# ADC.net
KiCad netlist of a schematic drawn in Altium Designer
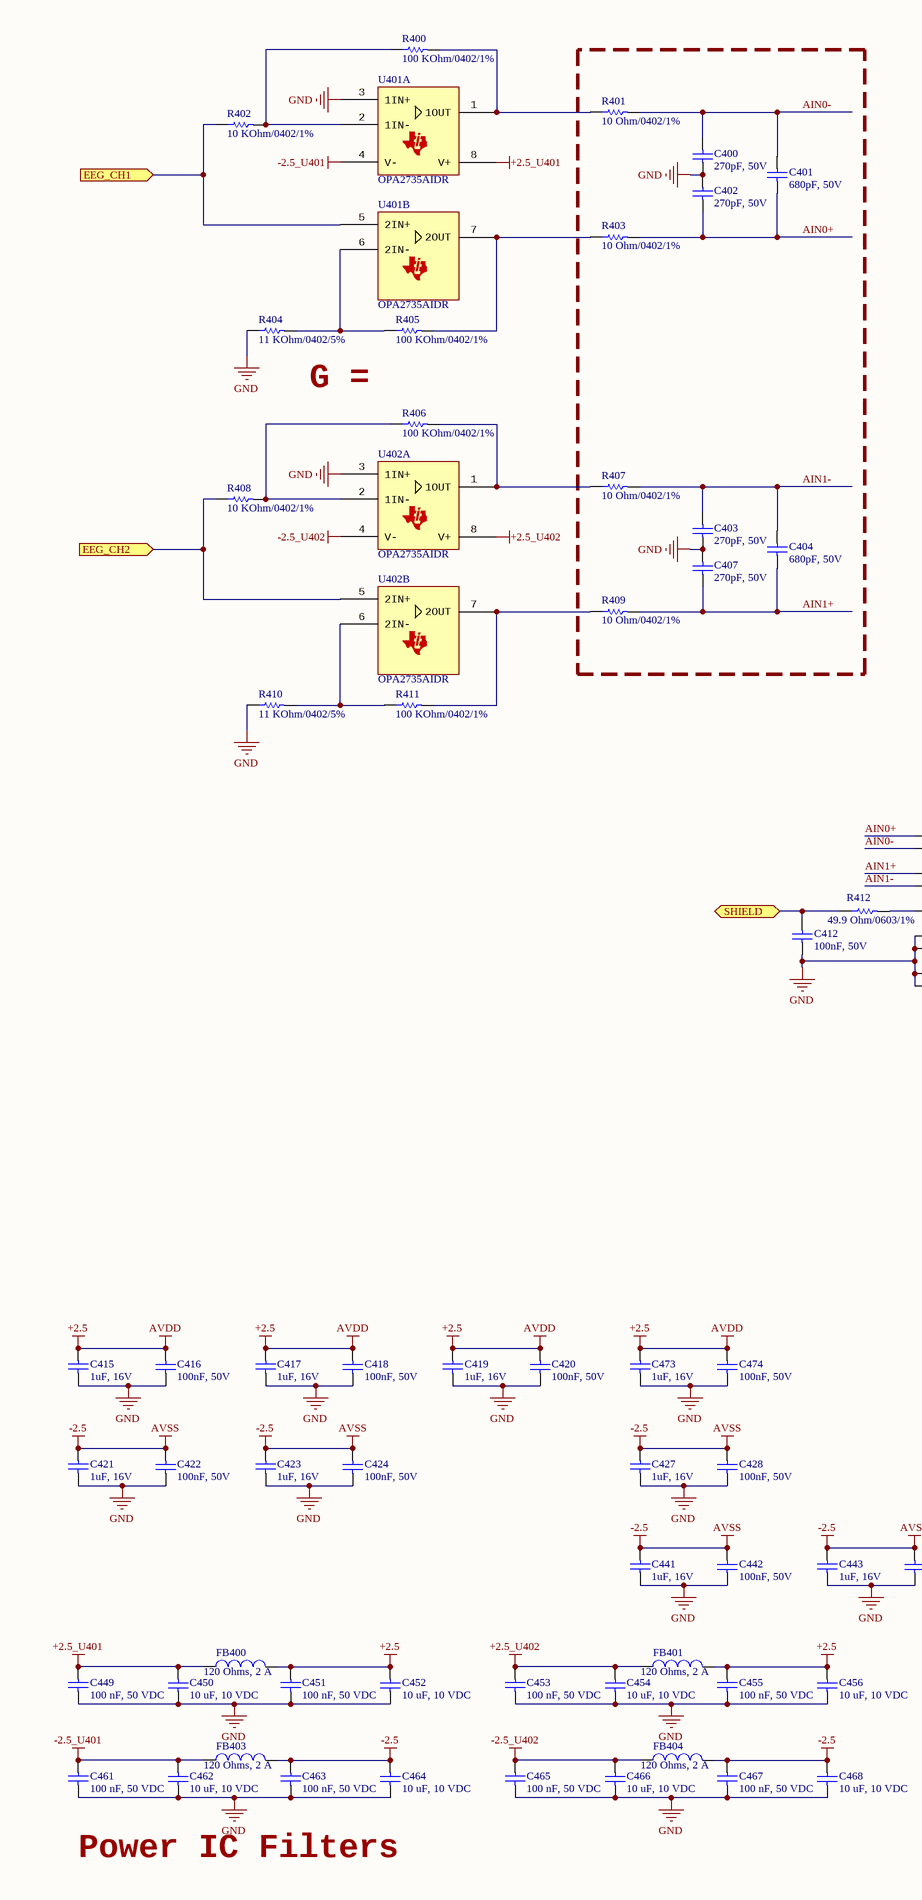
[diagram p0: ADC.SchDoc, left]
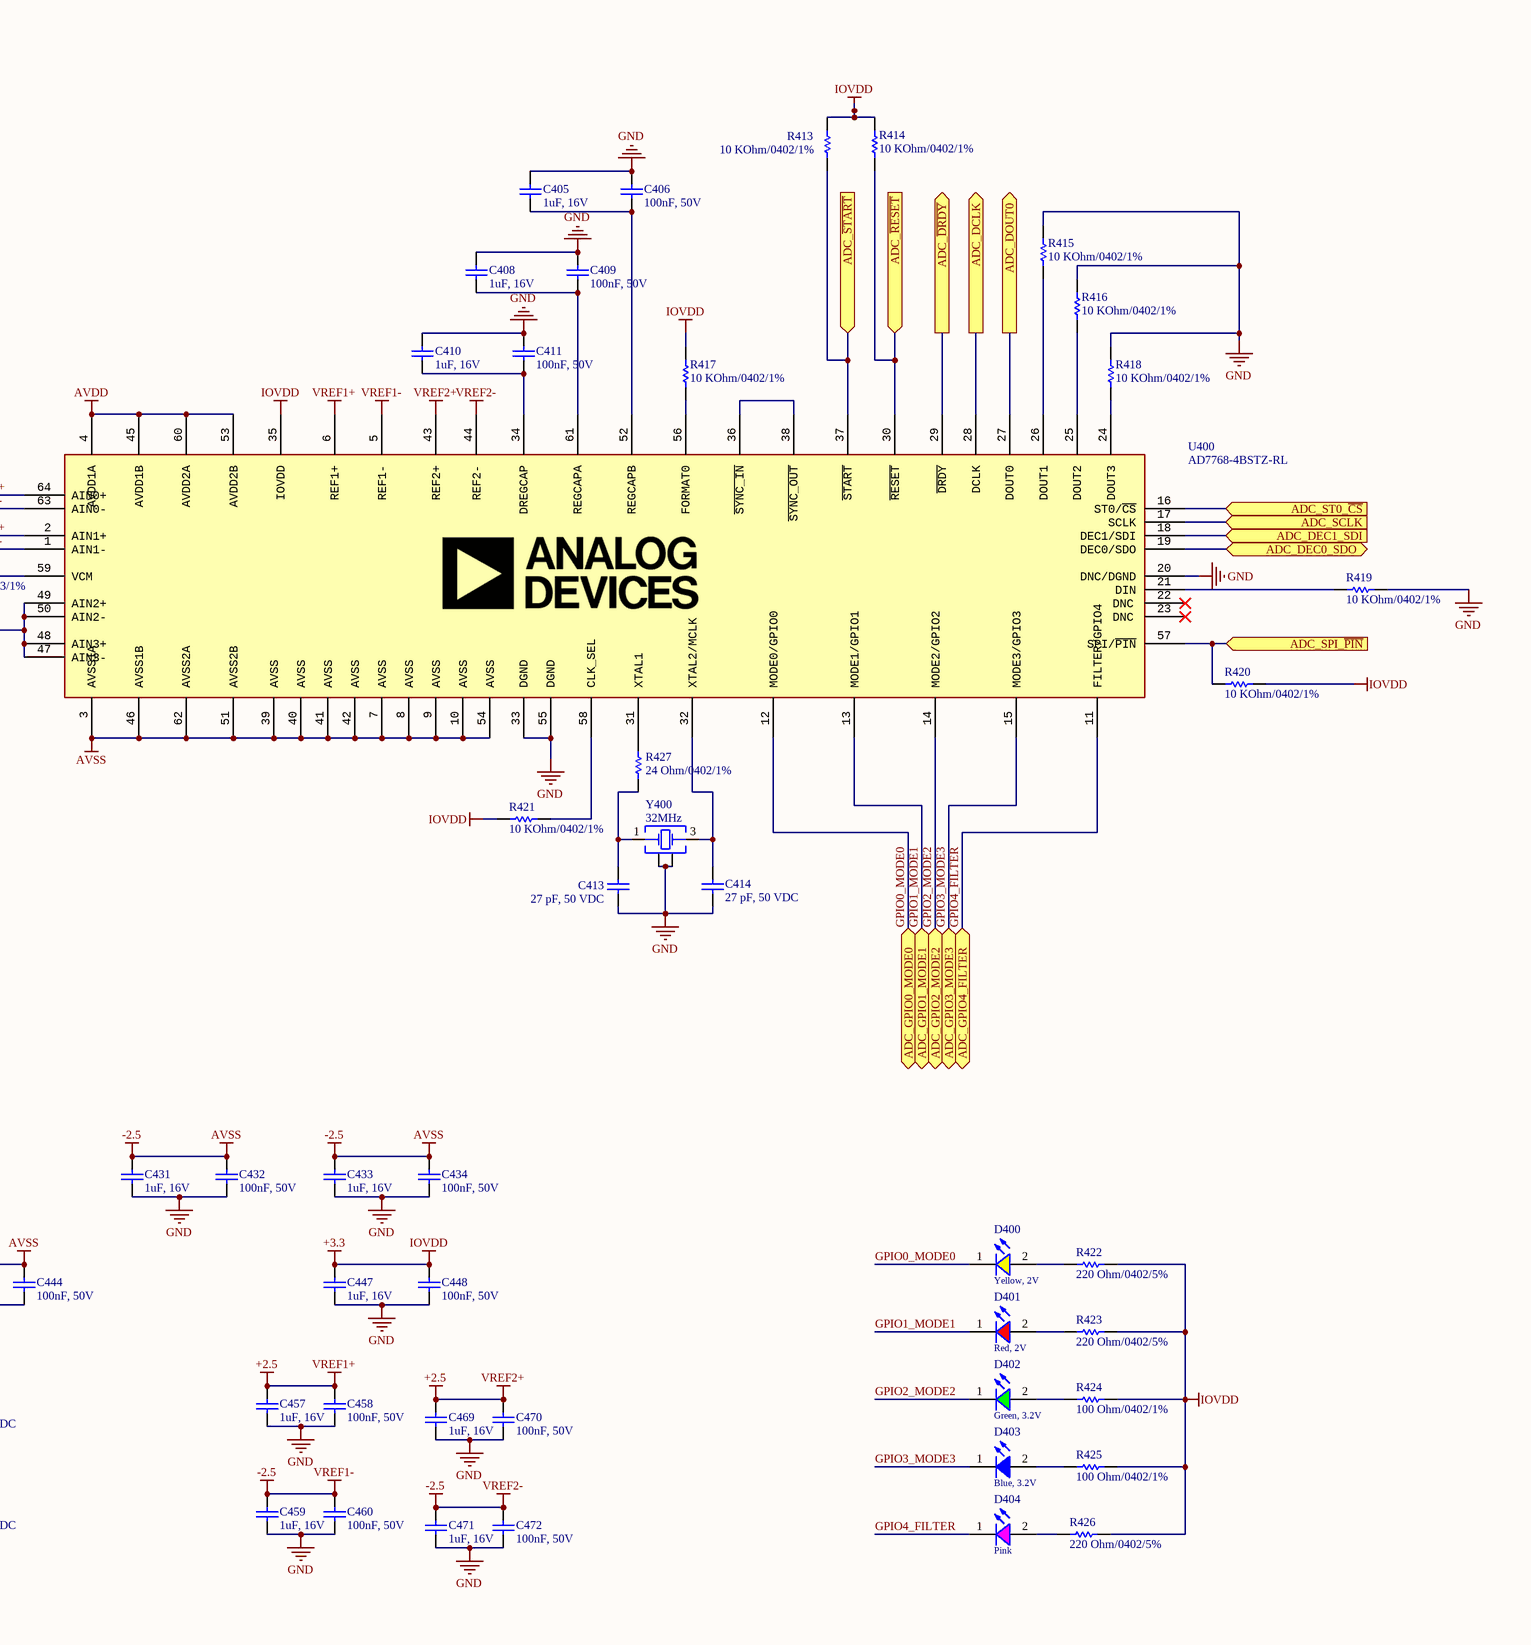
[diagram p1: ADC.SchDoc, right]

(export (version "E")
  (design (tool "Eeschema 10.0.6"))
  (components
    (comp (ref "C400")
      (value "270pF, 50V")
      (footprint "WCAP-CSGP_0402_L1W0.5H0.5")
      (description "WCAP-CSGP Multilayer Ceramic Chip Capacitor, General Purpose, size 0402, NP0, 270pF, 50V")
      (fields
        (field (name "MANUFACTURER PART NUMBER") "885012005063")
        (field (name "MANUFACTURER") "Wurth Elektronik")
      )
      (libsource (lib "Altium_WCAP-CSGP (rev24c)") (part "885012005063"))
    )
    (comp (ref "C401")
      (value "680pF, 50V")
      (footprint "WCAP-CSGP_0402_L1W0.5H0.5")
      (description "WCAP-CSGP Multilayer Ceramic Chip Capacitor, General Purpose, size 0402, X7R, 680pF, 50V")
      (fields
        (field (name "MANUFACTURER PART NUMBER") "885012205060")
        (field (name "MANUFACTURER") "Wurth Elektronik")
      )
      (libsource (lib "Altium_WCAP-CSGP (rev24c)") (part "885012205060"))
    )
    (comp (ref "C402")
      (value "270pF, 50V")
      (footprint "WCAP-CSGP_0402_L1W0.5H0.5")
      (description "WCAP-CSGP Multilayer Ceramic Chip Capacitor, General Purpose, size 0402, NP0, 270pF, 50V")
      (fields
        (field (name "MANUFACTURER PART NUMBER") "885012005063")
        (field (name "MANUFACTURER") "Wurth Elektronik")
      )
      (libsource (lib "Altium_WCAP-CSGP (rev24c)") (part "885012005063"))
    )
    (comp (ref "C403")
      (value "270pF, 50V")
      (footprint "WCAP-CSGP_0402_L1W0.5H0.5")
      (description "WCAP-CSGP Multilayer Ceramic Chip Capacitor, General Purpose, size 0402, NP0, 270pF, 50V")
      (fields
        (field (name "MANUFACTURER PART NUMBER") "885012005063")
        (field (name "MANUFACTURER") "Wurth Elektronik")
      )
      (libsource (lib "Altium_WCAP-CSGP (rev24c)") (part "885012005063"))
    )
    (comp (ref "C404")
      (value "680pF, 50V")
      (footprint "WCAP-CSGP_0402_L1W0.5H0.5")
      (description "WCAP-CSGP Multilayer Ceramic Chip Capacitor, General Purpose, size 0402, X7R, 680pF, 50V")
      (fields
        (field (name "MANUFACTURER PART NUMBER") "885012205060")
        (field (name "MANUFACTURER") "Wurth Elektronik")
      )
      (libsource (lib "Altium_WCAP-CSGP (rev24c)") (part "885012205060"))
    )
    (comp (ref "C405")
      (value "1uF, 16V")
      (footprint "WCAP-CSGP_0402_L1W0.5H0.5")
      (description "1 µF ±10% 16V Ceramic Capacitor X7R 0603 (1608 Metric)")
      (fields
        (field (name "MANUFACTURER PART NUMBER") "885012105012")
        (field (name "MANUFACTURER") "Wurth Elektronik")
      )
      (libsource (lib "Altium_WCAP-CSGP (rev24c)") (part "885012105012"))
    )
    (comp (ref "C406")
      (value "100nF, 50V")
      (footprint "WCAP-CSGP_0402_L1W0.5H0.5")
      (description "WCAP-CSGP Multilayer Ceramic Chip Capacitor, General Purpose, size 0402, X7R, 100nF, 50V")
      (fields
        (field (name "MANUFACTURER PART NUMBER") "885012205086")
        (field (name "MANUFACTURER") "Wurth Elektronik")
      )
      (libsource (lib "Altium_WCAP-CSGP (rev24c)") (part "885012205086"))
    )
    (comp (ref "C407")
      (value "270pF, 50V")
      (footprint "WCAP-CSGP_0402_L1W0.5H0.5")
      (description "WCAP-CSGP Multilayer Ceramic Chip Capacitor, General Purpose, size 0402, NP0, 270pF, 50V")
      (fields
        (field (name "MANUFACTURER PART NUMBER") "885012005063")
        (field (name "MANUFACTURER") "Wurth Elektronik")
      )
      (libsource (lib "Altium_WCAP-CSGP (rev24c)") (part "885012005063"))
    )
    (comp (ref "C408")
      (value "1uF, 16V")
      (footprint "WCAP-CSGP_0402_L1W0.5H0.5")
      (description "1 µF ±10% 16V Ceramic Capacitor X7R 0603 (1608 Metric)")
      (fields
        (field (name "MANUFACTURER PART NUMBER") "885012105012")
        (field (name "MANUFACTURER") "Wurth Elektronik")
      )
      (libsource (lib "Altium_WCAP-CSGP (rev24c)") (part "885012105012"))
    )
    (comp (ref "C409")
      (value "100nF, 50V")
      (footprint "WCAP-CSGP_0402_L1W0.5H0.5")
      (description "WCAP-CSGP Multilayer Ceramic Chip Capacitor, General Purpose, size 0402, X7R, 100nF, 50V")
      (fields
        (field (name "MANUFACTURER PART NUMBER") "885012205086")
        (field (name "MANUFACTURER") "Wurth Elektronik")
      )
      (libsource (lib "Altium_WCAP-CSGP (rev24c)") (part "885012205086"))
    )
    (comp (ref "C410")
      (value "1uF, 16V")
      (footprint "WCAP-CSGP_0402_L1W0.5H0.5")
      (description "1 µF ±10% 16V Ceramic Capacitor X7R 0603 (1608 Metric)")
      (fields
        (field (name "MANUFACTURER PART NUMBER") "885012105012")
        (field (name "MANUFACTURER") "Wurth Elektronik")
      )
      (libsource (lib "Altium_WCAP-CSGP (rev24c)") (part "885012105012"))
    )
    (comp (ref "C411")
      (value "100nF, 50V")
      (footprint "WCAP-CSGP_0402_L1W0.5H0.5")
      (description "WCAP-CSGP Multilayer Ceramic Chip Capacitor, General Purpose, size 0402, X7R, 100nF, 50V")
      (fields
        (field (name "MANUFACTURER PART NUMBER") "885012205086")
        (field (name "MANUFACTURER") "Wurth Elektronik")
      )
      (libsource (lib "Altium_WCAP-CSGP (rev24c)") (part "885012205086"))
    )
    (comp (ref "C412")
      (value "100nF, 50V")
      (footprint "WCAP-CSGP_0402_L1W0.5H0.5")
      (description "WCAP-CSGP Multilayer Ceramic Chip Capacitor, General Purpose, size 0402, X7R, 100nF, 50V")
      (fields
        (field (name "MANUFACTURER PART NUMBER") "885012205086")
        (field (name "MANUFACTURER") "Wurth Elektronik")
      )
      (libsource (lib "Altium_WCAP-CSGP (rev24c)") (part "885012205086"))
    )
    (comp (ref "C413")
      (value "27 pF, 50 VDC")
      (footprint "CAP_0603")
      (description "CAP, size 0603, 22 pF, 50 VDC")
      (fields (field (name "TOLERANCE") "+/-5%"))
      (libsource (lib "Altium_Ceramic_Cap") (part "0106032200550"))
    )
    (comp (ref "C414")
      (value "27 pF, 50 VDC")
      (footprint "CAP_0603")
      (description "CAP, size 0603, 22 pF, 50 VDC")
      (fields (field (name "TOLERANCE") "+/-5%"))
      (libsource (lib "Altium_Ceramic_Cap") (part "0106032200550"))
    )
    (comp (ref "C415")
      (value "1uF, 16V")
      (footprint "WCAP-CSGP_0402_L1W0.5H0.5")
      (description "1 µF ±10% 16V Ceramic Capacitor X7R 0603 (1608 Metric)")
      (fields
        (field (name "MANUFACTURER PART NUMBER") "885012105012")
        (field (name "MANUFACTURER") "Wurth Elektronik")
      )
      (libsource (lib "Altium_WCAP-CSGP (rev24c)") (part "885012105012"))
    )
    (comp (ref "C416")
      (value "100nF, 50V")
      (footprint "WCAP-CSGP_0402_L1W0.5H0.5")
      (description "WCAP-CSGP Multilayer Ceramic Chip Capacitor, General Purpose, size 0402, X7R, 100nF, 50V")
      (fields
        (field (name "MANUFACTURER PART NUMBER") "885012205086")
        (field (name "MANUFACTURER") "Wurth Elektronik")
      )
      (libsource (lib "Altium_WCAP-CSGP (rev24c)") (part "885012205086"))
    )
    (comp (ref "C417")
      (value "1uF, 16V")
      (footprint "WCAP-CSGP_0402_L1W0.5H0.5")
      (description "1 µF ±10% 16V Ceramic Capacitor X7R 0603 (1608 Metric)")
      (fields
        (field (name "MANUFACTURER PART NUMBER") "885012105012")
        (field (name "MANUFACTURER") "Wurth Elektronik")
      )
      (libsource (lib "Altium_WCAP-CSGP (rev24c)") (part "885012105012"))
    )
    (comp (ref "C418")
      (value "100nF, 50V")
      (footprint "WCAP-CSGP_0402_L1W0.5H0.5")
      (description "WCAP-CSGP Multilayer Ceramic Chip Capacitor, General Purpose, size 0402, X7R, 100nF, 50V")
      (fields
        (field (name "MANUFACTURER PART NUMBER") "885012205086")
        (field (name "MANUFACTURER") "Wurth Elektronik")
      )
      (libsource (lib "Altium_WCAP-CSGP (rev24c)") (part "885012205086"))
    )
    (comp (ref "C419")
      (value "1uF, 16V")
      (footprint "WCAP-CSGP_0402_L1W0.5H0.5")
      (description "1 µF ±10% 16V Ceramic Capacitor X7R 0603 (1608 Metric)")
      (fields
        (field (name "MANUFACTURER PART NUMBER") "885012105012")
        (field (name "MANUFACTURER") "Wurth Elektronik")
      )
      (libsource (lib "Altium_WCAP-CSGP (rev24c)") (part "885012105012"))
    )
    (comp (ref "C420")
      (value "100nF, 50V")
      (footprint "WCAP-CSGP_0402_L1W0.5H0.5")
      (description "WCAP-CSGP Multilayer Ceramic Chip Capacitor, General Purpose, size 0402, X7R, 100nF, 50V")
      (fields
        (field (name "MANUFACTURER PART NUMBER") "885012205086")
        (field (name "MANUFACTURER") "Wurth Elektronik")
      )
      (libsource (lib "Altium_WCAP-CSGP (rev24c)") (part "885012205086"))
    )
    (comp (ref "C421")
      (value "1uF, 16V")
      (footprint "WCAP-CSGP_0402_L1W0.5H0.5")
      (description "1 µF ±10% 16V Ceramic Capacitor X7R 0603 (1608 Metric)")
      (fields
        (field (name "MANUFACTURER PART NUMBER") "885012105012")
        (field (name "MANUFACTURER") "Wurth Elektronik")
      )
      (libsource (lib "Altium_WCAP-CSGP (rev24c)") (part "885012105012"))
    )
    (comp (ref "C422")
      (value "100nF, 50V")
      (footprint "WCAP-CSGP_0402_L1W0.5H0.5")
      (description "WCAP-CSGP Multilayer Ceramic Chip Capacitor, General Purpose, size 0402, X7R, 100nF, 50V")
      (fields
        (field (name "MANUFACTURER PART NUMBER") "885012205086")
        (field (name "MANUFACTURER") "Wurth Elektronik")
      )
      (libsource (lib "Altium_WCAP-CSGP (rev24c)") (part "885012205086"))
    )
    (comp (ref "C423")
      (value "1uF, 16V")
      (footprint "WCAP-CSGP_0402_L1W0.5H0.5")
      (description "1 µF ±10% 16V Ceramic Capacitor X7R 0603 (1608 Metric)")
      (fields
        (field (name "MANUFACTURER PART NUMBER") "885012105012")
        (field (name "MANUFACTURER") "Wurth Elektronik")
      )
      (libsource (lib "Altium_WCAP-CSGP (rev24c)") (part "885012105012"))
    )
    (comp (ref "C424")
      (value "100nF, 50V")
      (footprint "WCAP-CSGP_0402_L1W0.5H0.5")
      (description "WCAP-CSGP Multilayer Ceramic Chip Capacitor, General Purpose, size 0402, X7R, 100nF, 50V")
      (fields
        (field (name "MANUFACTURER PART NUMBER") "885012205086")
        (field (name "MANUFACTURER") "Wurth Elektronik")
      )
      (libsource (lib "Altium_WCAP-CSGP (rev24c)") (part "885012205086"))
    )
    (comp (ref "C427")
      (value "1uF, 16V")
      (footprint "WCAP-CSGP_0402_L1W0.5H0.5")
      (description "1 µF ±10% 16V Ceramic Capacitor X7R 0603 (1608 Metric)")
      (fields
        (field (name "MANUFACTURER PART NUMBER") "885012105012")
        (field (name "MANUFACTURER") "Wurth Elektronik")
      )
      (libsource (lib "Altium_WCAP-CSGP (rev24c)") (part "885012105012"))
    )
    (comp (ref "C428")
      (value "100nF, 50V")
      (footprint "WCAP-CSGP_0402_L1W0.5H0.5")
      (description "WCAP-CSGP Multilayer Ceramic Chip Capacitor, General Purpose, size 0402, X7R, 100nF, 50V")
      (fields
        (field (name "MANUFACTURER PART NUMBER") "885012205086")
        (field (name "MANUFACTURER") "Wurth Elektronik")
      )
      (libsource (lib "Altium_WCAP-CSGP (rev24c)") (part "885012205086"))
    )
    (comp (ref "C431")
      (value "1uF, 16V")
      (footprint "WCAP-CSGP_0402_L1W0.5H0.5")
      (description "1 µF ±10% 16V Ceramic Capacitor X7R 0603 (1608 Metric)")
      (fields
        (field (name "MANUFACTURER PART NUMBER") "885012105012")
        (field (name "MANUFACTURER") "Wurth Elektronik")
      )
      (libsource (lib "Altium_WCAP-CSGP (rev24c)") (part "885012105012"))
    )
    (comp (ref "C432")
      (value "100nF, 50V")
      (footprint "WCAP-CSGP_0402_L1W0.5H0.5")
      (description "WCAP-CSGP Multilayer Ceramic Chip Capacitor, General Purpose, size 0402, X7R, 100nF, 50V")
      (fields
        (field (name "MANUFACTURER PART NUMBER") "885012205086")
        (field (name "MANUFACTURER") "Wurth Elektronik")
      )
      (libsource (lib "Altium_WCAP-CSGP (rev24c)") (part "885012205086"))
    )
    (comp (ref "C433")
      (value "1uF, 16V")
      (footprint "WCAP-CSGP_0402_L1W0.5H0.5")
      (description "1 µF ±10% 16V Ceramic Capacitor X7R 0603 (1608 Metric)")
      (fields
        (field (name "MANUFACTURER PART NUMBER") "885012105012")
        (field (name "MANUFACTURER") "Wurth Elektronik")
      )
      (libsource (lib "Altium_WCAP-CSGP (rev24c)") (part "885012105012"))
    )
    (comp (ref "C434")
      (value "100nF, 50V")
      (footprint "WCAP-CSGP_0402_L1W0.5H0.5")
      (description "WCAP-CSGP Multilayer Ceramic Chip Capacitor, General Purpose, size 0402, X7R, 100nF, 50V")
      (fields
        (field (name "MANUFACTURER PART NUMBER") "885012205086")
        (field (name "MANUFACTURER") "Wurth Elektronik")
      )
      (libsource (lib "Altium_WCAP-CSGP (rev24c)") (part "885012205086"))
    )
    (comp (ref "C441")
      (value "1uF, 16V")
      (footprint "WCAP-CSGP_0402_L1W0.5H0.5")
      (description "1 µF ±10% 16V Ceramic Capacitor X7R 0603 (1608 Metric)")
      (fields
        (field (name "MANUFACTURER PART NUMBER") "885012105012")
        (field (name "MANUFACTURER") "Wurth Elektronik")
      )
      (libsource (lib "Altium_WCAP-CSGP (rev24c)") (part "885012105012"))
    )
    (comp (ref "C442")
      (value "100nF, 50V")
      (footprint "WCAP-CSGP_0402_L1W0.5H0.5")
      (description "WCAP-CSGP Multilayer Ceramic Chip Capacitor, General Purpose, size 0402, X7R, 100nF, 50V")
      (fields
        (field (name "MANUFACTURER PART NUMBER") "885012205086")
        (field (name "MANUFACTURER") "Wurth Elektronik")
      )
      (libsource (lib "Altium_WCAP-CSGP (rev24c)") (part "885012205086"))
    )
    (comp (ref "C443")
      (value "1uF, 16V")
      (footprint "WCAP-CSGP_0402_L1W0.5H0.5")
      (description "1 µF ±10% 16V Ceramic Capacitor X7R 0603 (1608 Metric)")
      (fields
        (field (name "MANUFACTURER PART NUMBER") "885012105012")
        (field (name "MANUFACTURER") "Wurth Elektronik")
      )
      (libsource (lib "Altium_WCAP-CSGP (rev24c)") (part "885012105012"))
    )
    (comp (ref "C444")
      (value "100nF, 50V")
      (footprint "WCAP-CSGP_0402_L1W0.5H0.5")
      (description "WCAP-CSGP Multilayer Ceramic Chip Capacitor, General Purpose, size 0402, X7R, 100nF, 50V")
      (fields
        (field (name "MANUFACTURER PART NUMBER") "885012205086")
        (field (name "MANUFACTURER") "Wurth Elektronik")
      )
      (libsource (lib "Altium_WCAP-CSGP (rev24c)") (part "885012205086"))
    )
    (comp (ref "C447")
      (value "1uF, 16V")
      (footprint "WCAP-CSGP_0402_L1W0.5H0.5")
      (description "1 µF ±10% 16V Ceramic Capacitor X7R 0603 (1608 Metric)")
      (fields
        (field (name "MANUFACTURER PART NUMBER") "885012105012")
        (field (name "MANUFACTURER") "Wurth Elektronik")
      )
      (libsource (lib "Altium_WCAP-CSGP (rev24c)") (part "885012105012"))
    )
    (comp (ref "C448")
      (value "100nF, 50V")
      (footprint "WCAP-CSGP_0402_L1W0.5H0.5")
      (description "WCAP-CSGP Multilayer Ceramic Chip Capacitor, General Purpose, size 0402, X7R, 100nF, 50V")
      (fields
        (field (name "MANUFACTURER PART NUMBER") "885012205086")
        (field (name "MANUFACTURER") "Wurth Elektronik")
      )
      (libsource (lib "Altium_WCAP-CSGP (rev24c)") (part "885012205086"))
    )
    (comp (ref "C449")
      (value "100 nF, 50 VDC")
      (footprint "CAP_0603")
      (description "CAP, size 0603, 100 nF, 50 VDC")
      (fields (field (name "TOLERANCE") "+/-10%"))
      (libsource (lib "Altium_Ceramic_Cap") (part "0106031041050"))
    )
    (comp (ref "C450")
      (value "10 uF, 10 VDC")
      (footprint "CAP_0603")
      (description "CAP, size 0603, 10 uF, 10 VDC")
      (fields (field (name "TOLERANCE") "+/-10%"))
      (libsource (lib "Altium_Ceramic_Cap") (part "0106031061010"))
    )
    (comp (ref "C451")
      (value "100 nF, 50 VDC")
      (footprint "CAP_0603")
      (description "CAP, size 0603, 100 nF, 50 VDC")
      (fields (field (name "TOLERANCE") "+/-10%"))
      (libsource (lib "Altium_Ceramic_Cap") (part "0106031041050"))
    )
    (comp (ref "C452")
      (value "10 uF, 10 VDC")
      (footprint "CAP_0603")
      (description "CAP, size 0603, 10 uF, 10 VDC")
      (fields (field (name "TOLERANCE") "+/-10%"))
      (libsource (lib "Altium_Ceramic_Cap") (part "0106031061010"))
    )
    (comp (ref "C453")
      (value "100 nF, 50 VDC")
      (footprint "CAP_0603")
      (description "CAP, size 0603, 100 nF, 50 VDC")
      (fields (field (name "TOLERANCE") "+/-10%"))
      (libsource (lib "Altium_Ceramic_Cap") (part "0106031041050"))
    )
    (comp (ref "C454")
      (value "10 uF, 10 VDC")
      (footprint "CAP_0603")
      (description "CAP, size 0603, 10 uF, 10 VDC")
      (fields (field (name "TOLERANCE") "+/-10%"))
      (libsource (lib "Altium_Ceramic_Cap") (part "0106031061010"))
    )
    (comp (ref "C455")
      (value "100 nF, 50 VDC")
      (footprint "CAP_0603")
      (description "CAP, size 0603, 100 nF, 50 VDC")
      (fields (field (name "TOLERANCE") "+/-10%"))
      (libsource (lib "Altium_Ceramic_Cap") (part "0106031041050"))
    )
    (comp (ref "C456")
      (value "10 uF, 10 VDC")
      (footprint "CAP_0603")
      (description "CAP, size 0603, 10 uF, 10 VDC")
      (fields (field (name "TOLERANCE") "+/-10%"))
      (libsource (lib "Altium_Ceramic_Cap") (part "0106031061010"))
    )
    (comp (ref "C457")
      (value "1uF, 16V")
      (footprint "WCAP-CSGP_0402_L1W0.5H0.5")
      (description "1 µF ±10% 16V Ceramic Capacitor X7R 0603 (1608 Metric)")
      (fields
        (field (name "MANUFACTURER PART NUMBER") "885012105012")
        (field (name "MANUFACTURER") "Wurth Elektronik")
      )
      (libsource (lib "Altium_WCAP-CSGP (rev24c)") (part "885012105012"))
    )
    (comp (ref "C458")
      (value "100nF, 50V")
      (footprint "WCAP-CSGP_0402_L1W0.5H0.5")
      (description "WCAP-CSGP Multilayer Ceramic Chip Capacitor, General Purpose, size 0402, X7R, 100nF, 50V")
      (fields
        (field (name "MANUFACTURER PART NUMBER") "885012205086")
        (field (name "MANUFACTURER") "Wurth Elektronik")
      )
      (libsource (lib "Altium_WCAP-CSGP (rev24c)") (part "885012205086"))
    )
    (comp (ref "C459")
      (value "1uF, 16V")
      (footprint "WCAP-CSGP_0402_L1W0.5H0.5")
      (description "1 µF ±10% 16V Ceramic Capacitor X7R 0603 (1608 Metric)")
      (fields
        (field (name "MANUFACTURER PART NUMBER") "885012105012")
        (field (name "MANUFACTURER") "Wurth Elektronik")
      )
      (libsource (lib "Altium_WCAP-CSGP (rev24c)") (part "885012105012"))
    )
    (comp (ref "C460")
      (value "100nF, 50V")
      (footprint "WCAP-CSGP_0402_L1W0.5H0.5")
      (description "WCAP-CSGP Multilayer Ceramic Chip Capacitor, General Purpose, size 0402, X7R, 100nF, 50V")
      (fields
        (field (name "MANUFACTURER PART NUMBER") "885012205086")
        (field (name "MANUFACTURER") "Wurth Elektronik")
      )
      (libsource (lib "Altium_WCAP-CSGP (rev24c)") (part "885012205086"))
    )
    (comp (ref "C461")
      (value "100 nF, 50 VDC")
      (footprint "CAP_0603")
      (description "CAP, size 0603, 100 nF, 50 VDC")
      (fields (field (name "TOLERANCE") "+/-10%"))
      (libsource (lib "Altium_Ceramic_Cap") (part "0106031041050"))
    )
    (comp (ref "C462")
      (value "10 uF, 10 VDC")
      (footprint "CAP_0603")
      (description "CAP, size 0603, 10 uF, 10 VDC")
      (fields (field (name "TOLERANCE") "+/-10%"))
      (libsource (lib "Altium_Ceramic_Cap") (part "0106031061010"))
    )
    (comp (ref "C463")
      (value "100 nF, 50 VDC")
      (footprint "CAP_0603")
      (description "CAP, size 0603, 100 nF, 50 VDC")
      (fields (field (name "TOLERANCE") "+/-10%"))
      (libsource (lib "Altium_Ceramic_Cap") (part "0106031041050"))
    )
    (comp (ref "C464")
      (value "10 uF, 10 VDC")
      (footprint "CAP_0603")
      (description "CAP, size 0603, 10 uF, 10 VDC")
      (fields (field (name "TOLERANCE") "+/-10%"))
      (libsource (lib "Altium_Ceramic_Cap") (part "0106031061010"))
    )
    (comp (ref "C465")
      (value "100 nF, 50 VDC")
      (footprint "CAP_0603")
      (description "CAP, size 0603, 100 nF, 50 VDC")
      (fields (field (name "TOLERANCE") "+/-10%"))
      (libsource (lib "Altium_Ceramic_Cap") (part "0106031041050"))
    )
    (comp (ref "C466")
      (value "10 uF, 10 VDC")
      (footprint "CAP_0603")
      (description "CAP, size 0603, 10 uF, 10 VDC")
      (fields (field (name "TOLERANCE") "+/-10%"))
      (libsource (lib "Altium_Ceramic_Cap") (part "0106031061010"))
    )
    (comp (ref "C467")
      (value "100 nF, 50 VDC")
      (footprint "CAP_0603")
      (description "CAP, size 0603, 100 nF, 50 VDC")
      (fields (field (name "TOLERANCE") "+/-10%"))
      (libsource (lib "Altium_Ceramic_Cap") (part "0106031041050"))
    )
    (comp (ref "C468")
      (value "10 uF, 10 VDC")
      (footprint "CAP_0603")
      (description "CAP, size 0603, 10 uF, 10 VDC")
      (fields (field (name "TOLERANCE") "+/-10%"))
      (libsource (lib "Altium_Ceramic_Cap") (part "0106031061010"))
    )
    (comp (ref "C469")
      (value "1uF, 16V")
      (footprint "WCAP-CSGP_0402_L1W0.5H0.5")
      (description "1 µF ±10% 16V Ceramic Capacitor X7R 0603 (1608 Metric)")
      (fields
        (field (name "MANUFACTURER PART NUMBER") "885012105012")
        (field (name "MANUFACTURER") "Wurth Elektronik")
      )
      (libsource (lib "Altium_WCAP-CSGP (rev24c)") (part "885012105012"))
    )
    (comp (ref "C470")
      (value "100nF, 50V")
      (footprint "WCAP-CSGP_0402_L1W0.5H0.5")
      (description "WCAP-CSGP Multilayer Ceramic Chip Capacitor, General Purpose, size 0402, X7R, 100nF, 50V")
      (fields
        (field (name "MANUFACTURER PART NUMBER") "885012205086")
        (field (name "MANUFACTURER") "Wurth Elektronik")
      )
      (libsource (lib "Altium_WCAP-CSGP (rev24c)") (part "885012205086"))
    )
    (comp (ref "C471")
      (value "1uF, 16V")
      (footprint "WCAP-CSGP_0402_L1W0.5H0.5")
      (description "1 µF ±10% 16V Ceramic Capacitor X7R 0603 (1608 Metric)")
      (fields
        (field (name "MANUFACTURER PART NUMBER") "885012105012")
        (field (name "MANUFACTURER") "Wurth Elektronik")
      )
      (libsource (lib "Altium_WCAP-CSGP (rev24c)") (part "885012105012"))
    )
    (comp (ref "C472")
      (value "100nF, 50V")
      (footprint "WCAP-CSGP_0402_L1W0.5H0.5")
      (description "WCAP-CSGP Multilayer Ceramic Chip Capacitor, General Purpose, size 0402, X7R, 100nF, 50V")
      (fields
        (field (name "MANUFACTURER PART NUMBER") "885012205086")
        (field (name "MANUFACTURER") "Wurth Elektronik")
      )
      (libsource (lib "Altium_WCAP-CSGP (rev24c)") (part "885012205086"))
    )
    (comp (ref "C473")
      (value "1uF, 16V")
      (footprint "WCAP-CSGP_0402_L1W0.5H0.5")
      (description "1 µF ±10% 16V Ceramic Capacitor X7R 0603 (1608 Metric)")
      (fields
        (field (name "MANUFACTURER PART NUMBER") "885012105012")
        (field (name "MANUFACTURER") "Wurth Elektronik")
      )
      (libsource (lib "Altium_WCAP-CSGP (rev24c)") (part "885012105012"))
    )
    (comp (ref "C474")
      (value "100nF, 50V")
      (footprint "WCAP-CSGP_0402_L1W0.5H0.5")
      (description "WCAP-CSGP Multilayer Ceramic Chip Capacitor, General Purpose, size 0402, X7R, 100nF, 50V")
      (fields
        (field (name "MANUFACTURER PART NUMBER") "885012205086")
        (field (name "MANUFACTURER") "Wurth Elektronik")
      )
      (libsource (lib "Altium_WCAP-CSGP (rev24c)") (part "885012205086"))
    )
    (comp (ref "D400")
      (value "Yellow, 2V")
      (footprint "WL-SMCW_0603_H=0.7mm")
      (description "WL-SMCW SMT Mono-color Chip LED Waterclear, size 0603, Yellow, 2V, 140deg")
      (libsource (lib "Altium_LED") (part "160603YellowClear"))
    )
    (comp (ref "D401")
      (value "Red, 2V")
      (footprint "WL-SMCW_0603_H=0.7mm")
      (description "WL-SMCW SMT Mono-color Chip LED Waterclear, size 0603, Red, 2V, 140deg")
      (libsource (lib "Altium_LED") (part "160603RedClear"))
    )
    (comp (ref "D402")
      (value "Green, 3.2V")
      (footprint "WL-SMCW_0603_H=0.7mm")
      (description "WL-SMCW SMT Mono-color Chip LED Waterclear, size 0603, Green, 3.2V, 140deg")
      (libsource (lib "Altium_LED") (part "160603GreenClear"))
    )
    (comp (ref "D403")
      (value "Blue, 3.2V")
      (footprint "WL-SMCW_0603_H=0.7mm")
      (description "WL-SMCW SMT Mono-color Chip LED Blur, size 0603, Blue, 3.2V, 140deg")
      (libsource (lib "Altium_LED") (part "160603BlueBlur"))
    )
    (comp (ref "D404")
      (value "Pink")
      (footprint "WL-SMCW_0603_H=0.7mm")
      (description "WL-SMCW SMT Mono-color Chip LED Blur, size 0603, Pink")
      (libsource (lib "Altium_LED") (part "160603PinkBlur"))
    )
    (comp (ref "FB400")
      (value "120 Ohms, 2 A")
      (footprint "FER_0603")
      (description "Ferrite, 0603, 120 Ohms, 2 A")
      (fields (field (name "TOLERANCE") "+/-25%"))
      (libsource (lib "Altium_Ferrite_Bead") (part "03060312120225"))
    )
    (comp (ref "FB401")
      (value "120 Ohms, 2 A")
      (footprint "FER_0603")
      (description "Ferrite, 0603, 120 Ohms, 2 A")
      (fields (field (name "TOLERANCE") "+/-25%"))
      (libsource (lib "Altium_Ferrite_Bead") (part "03060312120225"))
    )
    (comp (ref "FB403")
      (value "120 Ohms, 2 A")
      (footprint "FER_0603")
      (description "Ferrite, 0603, 120 Ohms, 2 A")
      (fields (field (name "TOLERANCE") "+/-25%"))
      (libsource (lib "Altium_Ferrite_Bead") (part "03060312120225"))
    )
    (comp (ref "FB404")
      (value "120 Ohms, 2 A")
      (footprint "FER_0603")
      (description "Ferrite, 0603, 120 Ohms, 2 A")
      (fields (field (name "TOLERANCE") "+/-25%"))
      (libsource (lib "Altium_Ferrite_Bead") (part "03060312120225"))
    )
    (comp (ref "R400")
      (value "100 KOhm/0402/1%")
      (footprint "R0402")
      (description "Code 104, 1/16W 1%")
      (fields (field (name "Comment") "Resistor 100 KOhm 0402 1%"))
      (libsource (lib "Giang_Resistor") (part "Resistor 100 KOhm 0402 1%"))
    )
    (comp (ref "R401")
      (value "10 Ohm/0402/1%")
      (footprint "R0402")
      (description "10 Ohms ±1% 0.063W, 1/16W Chip Resistor 0402 (1005 Metric) Moisture Resistant Thick Film")
      (fields (field (name "Comment") "Resistor 10 Ohm 0402 1%"))
      (libsource (lib "Giang_Resistor") (part "Resistor 10 Ohm 0402 1%"))
    )
    (comp (ref "R402")
      (value "10 KOhm/0402/1%")
      (footprint "R0402")
      (description "Code 103, 1/16W 1%")
      (fields (field (name "Comment") "Resistor 10 KOhm 0402 1%"))
      (libsource (lib "Giang_Resistor") (part "Resistor 10 KOhm 0402 1%"))
    )
    (comp (ref "R403")
      (value "10 Ohm/0402/1%")
      (footprint "R0402")
      (description "10 Ohms ±1% 0.063W, 1/16W Chip Resistor 0402 (1005 Metric) Moisture Resistant Thick Film")
      (fields (field (name "Comment") "Resistor 10 Ohm 0402 1%"))
      (libsource (lib "Giang_Resistor") (part "Resistor 10 Ohm 0402 1%"))
    )
    (comp (ref "R404")
      (value "11 KOhm/0402/5%")
      (footprint "R0402")
      (description "Code 113, 1/16W 5%")
      (fields (field (name "Comment") "Resistor 11 KOhm 0402 5%"))
      (libsource (lib "Giang_Resistor") (part "Resistor 11 KOhm 0402 5%"))
    )
    (comp (ref "R405")
      (value "100 KOhm/0402/1%")
      (footprint "R0402")
      (description "Code 104, 1/16W 1%")
      (fields (field (name "Comment") "Resistor 100 KOhm 0402 1%"))
      (libsource (lib "Giang_Resistor") (part "Resistor 100 KOhm 0402 1%"))
    )
    (comp (ref "R406")
      (value "100 KOhm/0402/1%")
      (footprint "R0402")
      (description "Code 104, 1/16W 1%")
      (fields (field (name "Comment") "Resistor 100 KOhm 0402 1%"))
      (libsource (lib "Giang_Resistor") (part "Resistor 100 KOhm 0402 1%"))
    )
    (comp (ref "R407")
      (value "10 Ohm/0402/1%")
      (footprint "R0402")
      (description "10 Ohms ±1% 0.063W, 1/16W Chip Resistor 0402 (1005 Metric) Moisture Resistant Thick Film")
      (fields (field (name "Comment") "Resistor 10 Ohm 0402 1%"))
      (libsource (lib "Giang_Resistor") (part "Resistor 10 Ohm 0402 1%"))
    )
    (comp (ref "R408")
      (value "10 KOhm/0402/1%")
      (footprint "R0402")
      (description "Code 103, 1/16W 1%")
      (fields (field (name "Comment") "Resistor 10 KOhm 0402 1%"))
      (libsource (lib "Giang_Resistor") (part "Resistor 10 KOhm 0402 1%"))
    )
    (comp (ref "R409")
      (value "10 Ohm/0402/1%")
      (footprint "R0402")
      (description "10 Ohms ±1% 0.063W, 1/16W Chip Resistor 0402 (1005 Metric) Moisture Resistant Thick Film")
      (fields (field (name "Comment") "Resistor 10 Ohm 0402 1%"))
      (libsource (lib "Giang_Resistor") (part "Resistor 10 Ohm 0402 1%"))
    )
    (comp (ref "R410")
      (value "11 KOhm/0402/5%")
      (footprint "R0402")
      (description "Code 113, 1/16W 5%")
      (fields (field (name "Comment") "Resistor 11 KOhm 0402 5%"))
      (libsource (lib "Giang_Resistor") (part "Resistor 11 KOhm 0402 5%"))
    )
    (comp (ref "R411")
      (value "100 KOhm/0402/1%")
      (footprint "R0402")
      (description "Code 104, 1/16W 1%")
      (fields (field (name "Comment") "Resistor 100 KOhm 0402 1%"))
      (libsource (lib "Giang_Resistor") (part "Resistor 100 KOhm 0402 1%"))
    )
    (comp (ref "R412")
      (value "49.9 Ohm/0603/1%")
      (footprint "R0603")
      (description "RM06FTN49R9")
      (fields (field (name "Comment") "Resistor 49.9 Ohm 0603 1%"))
      (libsource (lib "Giang_Resistor") (part "Resistor 49.9 Ohm 0603 1%"))
    )
    (comp (ref "R413")
      (value "10 KOhm/0402/1%")
      (footprint "R0402")
      (description "Code 103, 1/16W 1%")
      (fields (field (name "Comment") "Resistor 10 KOhm 0402 1%"))
      (libsource (lib "Giang_Resistor") (part "Resistor 10 KOhm 0402 1%"))
    )
    (comp (ref "R414")
      (value "10 KOhm/0402/1%")
      (footprint "R0402")
      (description "Code 103, 1/16W 1%")
      (fields (field (name "Comment") "Resistor 10 KOhm 0402 1%"))
      (libsource (lib "Giang_Resistor") (part "Resistor 10 KOhm 0402 1%"))
    )
    (comp (ref "R415")
      (value "10 KOhm/0402/1%")
      (footprint "R0402")
      (description "Code 103, 1/16W 1%")
      (fields (field (name "Comment") "Resistor 10 KOhm 0402 1%"))
      (libsource (lib "Giang_Resistor") (part "Resistor 10 KOhm 0402 1%"))
    )
    (comp (ref "R416")
      (value "10 KOhm/0402/1%")
      (footprint "R0402")
      (description "Code 103, 1/16W 1%")
      (fields (field (name "Comment") "Resistor 10 KOhm 0402 1%"))
      (libsource (lib "Giang_Resistor") (part "Resistor 10 KOhm 0402 1%"))
    )
    (comp (ref "R417")
      (value "10 KOhm/0402/1%")
      (footprint "R0402")
      (description "Code 103, 1/16W 1%")
      (fields (field (name "Comment") "Resistor 10 KOhm 0402 1%"))
      (libsource (lib "Giang_Resistor") (part "Resistor 10 KOhm 0402 1%"))
    )
    (comp (ref "R418")
      (value "10 KOhm/0402/1%")
      (footprint "R0402")
      (description "Code 103, 1/16W 1%")
      (fields (field (name "Comment") "Resistor 10 KOhm 0402 1%"))
      (libsource (lib "Giang_Resistor") (part "Resistor 10 KOhm 0402 1%"))
    )
    (comp (ref "R419")
      (value "10 KOhm/0402/1%")
      (footprint "R0402")
      (description "Code 103, 1/16W 1%")
      (fields (field (name "Comment") "Resistor 10 KOhm 0402 1%"))
      (libsource (lib "Giang_Resistor") (part "Resistor 10 KOhm 0402 1%"))
    )
    (comp (ref "R420")
      (value "10 KOhm/0402/1%")
      (footprint "R0402")
      (description "Code 103, 1/16W 1%")
      (fields (field (name "Comment") "Resistor 10 KOhm 0402 1%"))
      (libsource (lib "Giang_Resistor") (part "Resistor 10 KOhm 0402 1%"))
    )
    (comp (ref "R421")
      (value "10 KOhm/0402/1%")
      (footprint "R0402")
      (description "Code 103, 1/16W 1%")
      (fields (field (name "Comment") "Resistor 10 KOhm 0402 1%"))
      (libsource (lib "Giang_Resistor") (part "Resistor 10 KOhm 0402 1%"))
    )
    (comp (ref "R422")
      (value "220 Ohm/0402/5%")
      (footprint "R0402")
      (description "220R (Code 221), 1/16W 5% 0402")
      (fields (field (name "Comment") "Resistor 220 Ohm 0402 5%"))
      (libsource (lib "Giang_Resistor") (part "Resistor 220 Ohm 0402 5%"))
    )
    (comp (ref "R423")
      (value "220 Ohm/0402/5%")
      (footprint "R0402")
      (description "220R (Code 221), 1/16W 5% 0402")
      (fields (field (name "Comment") "Resistor 220 Ohm 0402 5%"))
      (libsource (lib "Giang_Resistor") (part "Resistor 220 Ohm 0402 5%"))
    )
    (comp (ref "R424")
      (value "100 Ohm/0402/1%")
      (footprint "R0402")
      (description "Code 104, 1/16W")
      (fields (field (name "Comment") "Resistor 100 Ohm 0402 1%"))
      (libsource (lib "Giang_Resistor") (part "Resistor 100 Ohm 0402 1%"))
    )
    (comp (ref "R425")
      (value "100 Ohm/0402/1%")
      (footprint "R0402")
      (description "Code 104, 1/16W")
      (fields (field (name "Comment") "Resistor 100 Ohm 0402 1%"))
      (libsource (lib "Giang_Resistor") (part "Resistor 100 Ohm 0402 1%"))
    )
    (comp (ref "R426")
      (value "220 Ohm/0402/5%")
      (footprint "R0402")
      (description "220R (Code 221), 1/16W 5% 0402")
      (fields (field (name "Comment") "Resistor 220 Ohm 0402 5%"))
      (libsource (lib "Giang_Resistor") (part "Resistor 220 Ohm 0402 5%"))
    )
    (comp (ref "R427")
      (value "24 Ohm/0402/1%")
      (footprint "R0402")
      (description "1/16W Thick Film Resistors 50V ±5% ±200ppm/℃ 24Ω 0402 Chip Resistor - Surface Mount ROHS")
      (fields (field (name "Comment") "Resistor 24 Ohm 0402 1%"))
      (libsource (lib "Giang_Resistor") (part "Resistor 24 Ohm 0402 1%"))
    )
    (comp (ref "U400")
      (value "AD7768-4BSTZ-RL")
      (footprint "ST-64-2_ADI")
      (description "24 Bit Analog to Digital Converter 4 Input 4 Sigma-Delta 64-LQFP (10x10)")
      (fields (field (name "Comment") "24 Bit Analog to Digital Converter 4 Input 4 Sigma-Delta"))
      (libsource (lib "Giang_ADC") (part "AD7768-4BSTZ-RL"))
    )
    (comp (ref "U401")
      (value "OPA2735AIDR")
      (footprint "SOIC-8")
      (description "0.05μV/°C max, Single-Supply CMOS Operational Amplifiers Zero-drift Series")
      (libsource (lib "Giang_Amplifiers") (part "OPA2735AIDR"))
    )
    (comp (ref "U402")
      (value "OPA2735AIDR")
      (footprint "SOIC-8")
      (description "0.05μV/°C max, Single-Supply CMOS Operational Amplifiers Zero-drift Series")
      (libsource (lib "Giang_Amplifiers") (part "OPA2735AIDR"))
    )
    (comp (ref "Y400")
      (value "32MHz")
      (footprint "WE-XTAL_CFPX-104")
      (description "WE-XTAL Quartz Crystal, SMT, CFPX-104, 32MHz, +/-20ppm")
      (fields
        (field (name "MANUFACTURER PART NUMBER") "830059535")
        (field (name "MANUFACTURER") "Wurth Elektronik")
      )
      (libsource (lib "Altium_WE-XTAL (rev22a)") (part "830059535"))
    )
  )
  (nets
    (net (code "1") (name "+2.5") (class "Default")
      (node (ref "C415") (pin "1") (pinfunction "1_1") (pintype "passive"))
      (node (ref "C416") (pin "2") (pinfunction "2_2") (pintype "passive"))
      (node (ref "C417") (pin "1") (pinfunction "1_1") (pintype "passive"))
      (node (ref "C418") (pin "2") (pinfunction "2_2") (pintype "passive"))
      (node (ref "C419") (pin "1") (pinfunction "1_1") (pintype "passive"))
      (node (ref "C420") (pin "2") (pinfunction "2_2") (pintype "passive"))
      (node (ref "C451") (pin "1") (pinfunction "1_1") (pintype "passive"))
      (node (ref "C452") (pin "2") (pinfunction "2_2") (pintype "passive"))
      (node (ref "C455") (pin "1") (pinfunction "1_1") (pintype "passive"))
      (node (ref "C456") (pin "2") (pinfunction "2_2") (pintype "passive"))
      (node (ref "C457") (pin "1") (pinfunction "1_1") (pintype "passive"))
      (node (ref "C458") (pin "2") (pinfunction "2_2") (pintype "passive"))
      (node (ref "C469") (pin "1") (pinfunction "1_1") (pintype "passive"))
      (node (ref "C470") (pin "2") (pinfunction "2_2") (pintype "passive"))
      (node (ref "C473") (pin "1") (pinfunction "1_1") (pintype "passive"))
      (node (ref "C474") (pin "2") (pinfunction "2_2") (pintype "passive"))
      (node (ref "FB400") (pin "2") (pinfunction "2_2") (pintype "passive"))
      (node (ref "FB401") (pin "2") (pinfunction "2_2") (pintype "passive"))
      (node (ref "U400") (pin "4") (pinfunction "AVDD1A_4") (pintype "passive"))
      (node (ref "U400") (pin "43") (pinfunction "REF2+_43") (pintype "passive"))
      (node (ref "U400") (pin "45") (pinfunction "AVDD1B_45") (pintype "passive"))
      (node (ref "U400") (pin "53") (pinfunction "AVDD2B_53") (pintype "passive"))
      (node (ref "U400") (pin "6") (pinfunction "REF1+_6") (pintype "passive"))
      (node (ref "U400") (pin "60") (pinfunction "AVDD2A_60") (pintype "passive"))
    )
    (net (code "2") (name "+2.5_U401") (class "Default")
      (node (ref "C449") (pin "1") (pinfunction "1_1") (pintype "passive"))
      (node (ref "C450") (pin "2") (pinfunction "2_2") (pintype "passive"))
      (node (ref "FB400") (pin "1") (pinfunction "1_1") (pintype "passive"))
      (node (ref "U401") (pin "8") (pinfunction "V+_8") (pintype "passive"))
    )
    (net (code "3") (name "+2.5_U402") (class "Default")
      (node (ref "C453") (pin "1") (pinfunction "1_1") (pintype "passive"))
      (node (ref "C454") (pin "2") (pinfunction "2_2") (pintype "passive"))
      (node (ref "FB401") (pin "1") (pinfunction "1_1") (pintype "passive"))
      (node (ref "U402") (pin "8") (pinfunction "V+_8") (pintype "passive"))
    )
    (net (code "4") (name "+3.3") (class "Default")
      (node (ref "C447") (pin "1") (pinfunction "1_1") (pintype "passive"))
      (node (ref "C448") (pin "2") (pinfunction "2_2") (pintype "passive"))
      (node (ref "R413") (pin "1") (pinfunction "1_1") (pintype "passive"))
      (node (ref "R414") (pin "1") (pinfunction "1_1") (pintype "passive"))
      (node (ref "R417") (pin "1") (pinfunction "1_1") (pintype "passive"))
      (node (ref "R420") (pin "1") (pinfunction "1_1") (pintype "passive"))
      (node (ref "R421") (pin "2") (pinfunction "2_2") (pintype "passive"))
      (node (ref "R422") (pin "2") (pinfunction "2_2") (pintype "passive"))
      (node (ref "R423") (pin "2") (pinfunction "2_2") (pintype "passive"))
      (node (ref "R424") (pin "2") (pinfunction "2_2") (pintype "passive"))
      (node (ref "R425") (pin "2") (pinfunction "2_2") (pintype "passive"))
      (node (ref "R426") (pin "2") (pinfunction "2_2") (pintype "passive"))
      (node (ref "U400") (pin "35") (pinfunction "IOVDD_35") (pintype "passive"))
    )
    (net (code "5") (name "-2.5") (class "Default")
      (node (ref "C421") (pin "1") (pinfunction "1_1") (pintype "passive"))
      (node (ref "C422") (pin "2") (pinfunction "2_2") (pintype "passive"))
      (node (ref "C423") (pin "1") (pinfunction "1_1") (pintype "passive"))
      (node (ref "C424") (pin "2") (pinfunction "2_2") (pintype "passive"))
      (node (ref "C427") (pin "1") (pinfunction "1_1") (pintype "passive"))
      (node (ref "C428") (pin "2") (pinfunction "2_2") (pintype "passive"))
      (node (ref "C431") (pin "1") (pinfunction "1_1") (pintype "passive"))
      (node (ref "C432") (pin "2") (pinfunction "2_2") (pintype "passive"))
      (node (ref "C433") (pin "1") (pinfunction "1_1") (pintype "passive"))
      (node (ref "C434") (pin "2") (pinfunction "2_2") (pintype "passive"))
      (node (ref "C441") (pin "1") (pinfunction "1_1") (pintype "passive"))
      (node (ref "C442") (pin "2") (pinfunction "2_2") (pintype "passive"))
      (node (ref "C443") (pin "1") (pinfunction "1_1") (pintype "passive"))
      (node (ref "C444") (pin "2") (pinfunction "2_2") (pintype "passive"))
      (node (ref "C459") (pin "1") (pinfunction "1_1") (pintype "passive"))
      (node (ref "C460") (pin "2") (pinfunction "2_2") (pintype "passive"))
      (node (ref "C463") (pin "1") (pinfunction "1_1") (pintype "passive"))
      (node (ref "C464") (pin "2") (pinfunction "2_2") (pintype "passive"))
      (node (ref "C467") (pin "1") (pinfunction "1_1") (pintype "passive"))
      (node (ref "C468") (pin "2") (pinfunction "2_2") (pintype "passive"))
      (node (ref "C471") (pin "1") (pinfunction "1_1") (pintype "passive"))
      (node (ref "C472") (pin "2") (pinfunction "2_2") (pintype "passive"))
      (node (ref "FB403") (pin "2") (pinfunction "2_2") (pintype "passive"))
      (node (ref "FB404") (pin "2") (pinfunction "2_2") (pintype "passive"))
      (node (ref "U400") (pin "10") (pinfunction "AVSS_10") (pintype "passive"))
      (node (ref "U400") (pin "3") (pinfunction "AVSS1A_3") (pintype "passive"))
      (node (ref "U400") (pin "39") (pinfunction "AVSS_39") (pintype "passive"))
      (node (ref "U400") (pin "40") (pinfunction "AVSS_40") (pintype "passive"))
      (node (ref "U400") (pin "41") (pinfunction "AVSS_41") (pintype "passive"))
      (node (ref "U400") (pin "42") (pinfunction "AVSS_42") (pintype "passive"))
      (node (ref "U400") (pin "44") (pinfunction "REF2-_44") (pintype "passive"))
      (node (ref "U400") (pin "46") (pinfunction "AVSS1B_46") (pintype "passive"))
      (node (ref "U400") (pin "5") (pinfunction "REF1-_5") (pintype "passive"))
      (node (ref "U400") (pin "51") (pinfunction "AVSS2B_51") (pintype "passive"))
      (node (ref "U400") (pin "54") (pinfunction "AVSS_54") (pintype "passive"))
      (node (ref "U400") (pin "62") (pinfunction "AVSS2A_62") (pintype "passive"))
      (node (ref "U400") (pin "7") (pinfunction "AVSS_7") (pintype "passive"))
      (node (ref "U400") (pin "8") (pinfunction "AVSS_8") (pintype "passive"))
      (node (ref "U400") (pin "9") (pinfunction "AVSS_9") (pintype "passive"))
    )
    (net (code "6") (name "-2.5_U401") (class "Default")
      (node (ref "C461") (pin "1") (pinfunction "1_1") (pintype "passive"))
      (node (ref "C462") (pin "2") (pinfunction "2_2") (pintype "passive"))
      (node (ref "FB403") (pin "1") (pinfunction "1_1") (pintype "passive"))
      (node (ref "U401") (pin "4") (pinfunction "V-_4") (pintype "passive"))
    )
    (net (code "7") (name "-2.5_U402") (class "Default")
      (node (ref "C465") (pin "1") (pinfunction "1_1") (pintype "passive"))
      (node (ref "C466") (pin "2") (pinfunction "2_2") (pintype "passive"))
      (node (ref "FB404") (pin "1") (pinfunction "1_1") (pintype "passive"))
      (node (ref "U402") (pin "4") (pinfunction "V-_4") (pintype "passive"))
    )
    (net (code "8") (name "/ADC_DCLK") (class "Default")
      (node (ref "U400") (pin "28") (pinfunction "DCLK_28") (pintype "passive"))
    )
    (net (code "9") (name "/ADC_DEC0_SDO") (class "Default")
      (node (ref "U400") (pin "19") (pinfunction "DEC0/SDO_19") (pintype "passive"))
    )
    (net (code "10") (name "/ADC_DEC1_SDI") (class "Default")
      (node (ref "U400") (pin "18") (pinfunction "DEC1/SDI_18") (pintype "passive"))
    )
    (net (code "11") (name "/ADC_DOUT0") (class "Default")
      (node (ref "U400") (pin "27") (pinfunction "DOUT0_27") (pintype "passive"))
    )
    (net (code "12") (name "/ADC_SCLK") (class "Default")
      (node (ref "U400") (pin "17") (pinfunction "SCLK_17") (pintype "passive"))
    )
    (net (code "13") (name "/ADC_SPI_~{PIN}") (class "Default")
      (node (ref "R420") (pin "2") (pinfunction "2_2") (pintype "passive"))
      (node (ref "U400") (pin "57") (pinfunction "SPI/~{PIN}_57") (pintype "passive"))
    )
    (net (code "14") (name "/ADC_ST0_~{CS}") (class "Default")
      (node (ref "U400") (pin "16") (pinfunction "ST0/~{CS}_16") (pintype "passive"))
    )
    (net (code "15") (name "/ADC_~{DRDY}") (class "Default")
      (node (ref "U400") (pin "29") (pinfunction "~{DRDY}_29") (pintype "passive"))
    )
    (net (code "16") (name "/ADC_~{RESET}") (class "Default")
      (node (ref "R414") (pin "2") (pinfunction "2_2") (pintype "passive"))
      (node (ref "U400") (pin "30") (pinfunction "~{RESET}_30") (pintype "passive"))
    )
    (net (code "17") (name "/ADC_~{START}") (class "Default")
      (node (ref "R413") (pin "2") (pinfunction "2_2") (pintype "passive"))
      (node (ref "U400") (pin "37") (pinfunction "~{START}_37") (pintype "passive"))
    )
    (net (code "18") (name "/AIN0+") (class "Default")
      (node (ref "C401") (pin "1") (pinfunction "1_1") (pintype "passive"))
      (node (ref "C402") (pin "1") (pinfunction "1_1") (pintype "passive"))
      (node (ref "R403") (pin "2") (pinfunction "2_2") (pintype "passive"))
      (node (ref "U400") (pin "64") (pinfunction "AIN0+_64") (pintype "passive"))
    )
    (net (code "19") (name "/AIN0-") (class "Default")
      (node (ref "C400") (pin "2") (pinfunction "2_2") (pintype "passive"))
      (node (ref "C401") (pin "2") (pinfunction "2_2") (pintype "passive"))
      (node (ref "R401") (pin "2") (pinfunction "2_2") (pintype "passive"))
      (node (ref "U400") (pin "63") (pinfunction "AIN0-_63") (pintype "passive"))
    )
    (net (code "20") (name "/AIN1+") (class "Default")
      (node (ref "C404") (pin "1") (pinfunction "1_1") (pintype "passive"))
      (node (ref "C407") (pin "1") (pinfunction "1_1") (pintype "passive"))
      (node (ref "R409") (pin "2") (pinfunction "2_2") (pintype "passive"))
      (node (ref "U400") (pin "2") (pinfunction "AIN1+_2") (pintype "passive"))
    )
    (net (code "21") (name "/AIN1-") (class "Default")
      (node (ref "C403") (pin "2") (pinfunction "2_2") (pintype "passive"))
      (node (ref "C404") (pin "2") (pinfunction "2_2") (pintype "passive"))
      (node (ref "R407") (pin "2") (pinfunction "2_2") (pintype "passive"))
      (node (ref "U400") (pin "1") (pinfunction "AIN1-_1") (pintype "passive"))
    )
    (net (code "22") (name "/EEG_CH1") (class "Default")
      (node (ref "R402") (pin "1") (pinfunction "1_1") (pintype "passive"))
      (node (ref "U401") (pin "5") (pinfunction "2IN+_5") (pintype "passive"))
    )
    (net (code "23") (name "/EEG_CH2") (class "Default")
      (node (ref "R408") (pin "1") (pinfunction "1_1") (pintype "passive"))
      (node (ref "U402") (pin "5") (pinfunction "2IN+_5") (pintype "passive"))
    )
    (net (code "24") (name "/GPIO0_MODE0") (class "Default")
      (node (ref "D400") (pin "1") (pinfunction "K_1") (pintype "passive"))
      (node (ref "U400") (pin "12") (pinfunction "MODE0/GPIO0_12") (pintype "passive"))
    )
    (net (code "25") (name "/GPIO1_MODE1") (class "Default")
      (node (ref "D401") (pin "1") (pinfunction "K_1") (pintype "passive"))
      (node (ref "U400") (pin "13") (pinfunction "MODE1/GPIO1_13") (pintype "passive"))
    )
    (net (code "26") (name "/GPIO2_MODE2") (class "Default")
      (node (ref "D402") (pin "1") (pinfunction "K_1") (pintype "passive"))
      (node (ref "U400") (pin "14") (pinfunction "MODE2/GPIO2_14") (pintype "passive"))
    )
    (net (code "27") (name "/GPIO3_MODE3") (class "Default")
      (node (ref "D403") (pin "1") (pinfunction "K_1") (pintype "passive"))
      (node (ref "U400") (pin "15") (pinfunction "MODE3/GPIO3_15") (pintype "passive"))
    )
    (net (code "28") (name "/GPIO4_FILTER") (class "Default")
      (node (ref "D404") (pin "1") (pinfunction "K_1") (pintype "passive"))
      (node (ref "U400") (pin "11") (pinfunction "FILTER/GPIO4_11") (pintype "passive"))
    )
    (net (code "29") (name "/SHIELD") (class "Default")
      (node (ref "C412") (pin "2") (pinfunction "2_2") (pintype "passive"))
      (node (ref "R412") (pin "1") (pinfunction "1_1") (pintype "passive"))
    )
    (net (code "30") (name "GND") (class "Default")
      (node (ref "C400") (pin "1") (pinfunction "1_1") (pintype "passive"))
      (node (ref "C402") (pin "2") (pinfunction "2_2") (pintype "passive"))
      (node (ref "C403") (pin "1") (pinfunction "1_1") (pintype "passive"))
      (node (ref "C405") (pin "1") (pinfunction "1_1") (pintype "passive"))
      (node (ref "C406") (pin "2") (pinfunction "2_2") (pintype "passive"))
      (node (ref "C407") (pin "2") (pinfunction "2_2") (pintype "passive"))
      (node (ref "C408") (pin "1") (pinfunction "1_1") (pintype "passive"))
      (node (ref "C409") (pin "2") (pinfunction "2_2") (pintype "passive"))
      (node (ref "C410") (pin "1") (pinfunction "1_1") (pintype "passive"))
      (node (ref "C411") (pin "2") (pinfunction "2_2") (pintype "passive"))
      (node (ref "C412") (pin "1") (pinfunction "1_1") (pintype "passive"))
      (node (ref "C413") (pin "1") (pinfunction "1_1") (pintype "passive"))
      (node (ref "C414") (pin "1") (pinfunction "1_1") (pintype "passive"))
      (node (ref "C415") (pin "2") (pinfunction "2_2") (pintype "passive"))
      (node (ref "C416") (pin "1") (pinfunction "1_1") (pintype "passive"))
      (node (ref "C417") (pin "2") (pinfunction "2_2") (pintype "passive"))
      (node (ref "C418") (pin "1") (pinfunction "1_1") (pintype "passive"))
      (node (ref "C419") (pin "2") (pinfunction "2_2") (pintype "passive"))
      (node (ref "C420") (pin "1") (pinfunction "1_1") (pintype "passive"))
      (node (ref "C421") (pin "2") (pinfunction "2_2") (pintype "passive"))
      (node (ref "C422") (pin "1") (pinfunction "1_1") (pintype "passive"))
      (node (ref "C423") (pin "2") (pinfunction "2_2") (pintype "passive"))
      (node (ref "C424") (pin "1") (pinfunction "1_1") (pintype "passive"))
      (node (ref "C427") (pin "2") (pinfunction "2_2") (pintype "passive"))
      (node (ref "C428") (pin "1") (pinfunction "1_1") (pintype "passive"))
      (node (ref "C431") (pin "2") (pinfunction "2_2") (pintype "passive"))
      (node (ref "C432") (pin "1") (pinfunction "1_1") (pintype "passive"))
      (node (ref "C433") (pin "2") (pinfunction "2_2") (pintype "passive"))
      (node (ref "C434") (pin "1") (pinfunction "1_1") (pintype "passive"))
      (node (ref "C441") (pin "2") (pinfunction "2_2") (pintype "passive"))
      (node (ref "C442") (pin "1") (pinfunction "1_1") (pintype "passive"))
      (node (ref "C443") (pin "2") (pinfunction "2_2") (pintype "passive"))
      (node (ref "C444") (pin "1") (pinfunction "1_1") (pintype "passive"))
      (node (ref "C447") (pin "2") (pinfunction "2_2") (pintype "passive"))
      (node (ref "C448") (pin "1") (pinfunction "1_1") (pintype "passive"))
      (node (ref "C449") (pin "2") (pinfunction "2_2") (pintype "passive"))
      (node (ref "C450") (pin "1") (pinfunction "1_1") (pintype "passive"))
      (node (ref "C451") (pin "2") (pinfunction "2_2") (pintype "passive"))
      (node (ref "C452") (pin "1") (pinfunction "1_1") (pintype "passive"))
      (node (ref "C453") (pin "2") (pinfunction "2_2") (pintype "passive"))
      (node (ref "C454") (pin "1") (pinfunction "1_1") (pintype "passive"))
      (node (ref "C455") (pin "2") (pinfunction "2_2") (pintype "passive"))
      (node (ref "C456") (pin "1") (pinfunction "1_1") (pintype "passive"))
      (node (ref "C457") (pin "2") (pinfunction "2_2") (pintype "passive"))
      (node (ref "C458") (pin "1") (pinfunction "1_1") (pintype "passive"))
      (node (ref "C459") (pin "2") (pinfunction "2_2") (pintype "passive"))
      (node (ref "C460") (pin "1") (pinfunction "1_1") (pintype "passive"))
      (node (ref "C461") (pin "2") (pinfunction "2_2") (pintype "passive"))
      (node (ref "C462") (pin "1") (pinfunction "1_1") (pintype "passive"))
      (node (ref "C463") (pin "2") (pinfunction "2_2") (pintype "passive"))
      (node (ref "C464") (pin "1") (pinfunction "1_1") (pintype "passive"))
      (node (ref "C465") (pin "2") (pinfunction "2_2") (pintype "passive"))
      (node (ref "C466") (pin "1") (pinfunction "1_1") (pintype "passive"))
      (node (ref "C467") (pin "2") (pinfunction "2_2") (pintype "passive"))
      (node (ref "C468") (pin "1") (pinfunction "1_1") (pintype "passive"))
      (node (ref "C469") (pin "2") (pinfunction "2_2") (pintype "passive"))
      (node (ref "C470") (pin "1") (pinfunction "1_1") (pintype "passive"))
      (node (ref "C471") (pin "2") (pinfunction "2_2") (pintype "passive"))
      (node (ref "C472") (pin "1") (pinfunction "1_1") (pintype "passive"))
      (node (ref "C473") (pin "2") (pinfunction "2_2") (pintype "passive"))
      (node (ref "C474") (pin "1") (pinfunction "1_1") (pintype "passive"))
      (node (ref "R404") (pin "1") (pinfunction "1_1") (pintype "passive"))
      (node (ref "R410") (pin "1") (pinfunction "1_1") (pintype "passive"))
      (node (ref "R415") (pin "1") (pinfunction "1_1") (pintype "passive"))
      (node (ref "R416") (pin "1") (pinfunction "1_1") (pintype "passive"))
      (node (ref "R418") (pin "1") (pinfunction "1_1") (pintype "passive"))
      (node (ref "R419") (pin "1") (pinfunction "1_1") (pintype "passive"))
      (node (ref "U400") (pin "20") (pinfunction "DNC/DGND_20") (pintype "passive"))
      (node (ref "U400") (pin "33") (pinfunction "DGND_33") (pintype "passive"))
      (node (ref "U400") (pin "47") (pinfunction "AIN3-_47") (pintype "passive"))
      (node (ref "U400") (pin "48") (pinfunction "AIN3+_48") (pintype "passive"))
      (node (ref "U400") (pin "49") (pinfunction "AIN2+_49") (pintype "passive"))
      (node (ref "U400") (pin "50") (pinfunction "AIN2-_50") (pintype "passive"))
      (node (ref "U400") (pin "55") (pinfunction "DGND_55") (pintype "passive"))
      (node (ref "U401") (pin "3") (pinfunction "1IN+_3") (pintype "passive"))
      (node (ref "U402") (pin "3") (pinfunction "1IN+_3") (pintype "passive"))
      (node (ref "Y400") (pin "2") (pinfunction "GND_&_Lid_2") (pintype "passive"))
      (node (ref "Y400") (pin "4") (pinfunction "GND_&_Lid_4") (pintype "passive"))
    )
    (net (code "31") (name "Net-(C413-Pad2)") (class "Default")
      (node (ref "C413") (pin "2") (pinfunction "2_2") (pintype "passive"))
      (node (ref "R427") (pin "1") (pinfunction "1_1") (pintype "passive"))
      (node (ref "Y400") (pin "1") (pinfunction "Crystal_1") (pintype "passive"))
    )
    (net (code "32") (name "Net-(D400-A)") (class "Default")
      (node (ref "D400") (pin "2") (pinfunction "A_2") (pintype "passive"))
      (node (ref "R422") (pin "1") (pinfunction "1_1") (pintype "passive"))
    )
    (net (code "33") (name "Net-(D401-A)") (class "Default")
      (node (ref "D401") (pin "2") (pinfunction "A_2") (pintype "passive"))
      (node (ref "R423") (pin "1") (pinfunction "1_1") (pintype "passive"))
    )
    (net (code "34") (name "Net-(D402-A)") (class "Default")
      (node (ref "D402") (pin "2") (pinfunction "A_2") (pintype "passive"))
      (node (ref "R424") (pin "1") (pinfunction "1_1") (pintype "passive"))
    )
    (net (code "35") (name "Net-(D403-A)") (class "Default")
      (node (ref "D403") (pin "2") (pinfunction "A_2") (pintype "passive"))
      (node (ref "R425") (pin "1") (pinfunction "1_1") (pintype "passive"))
    )
    (net (code "36") (name "Net-(D404-A)") (class "Default")
      (node (ref "D404") (pin "2") (pinfunction "A_2") (pintype "passive"))
      (node (ref "R426") (pin "1") (pinfunction "1_1") (pintype "passive"))
    )
    (net (code "37") (name "Net-(U400-CLK_SEL)") (class "Default")
      (node (ref "R421") (pin "1") (pinfunction "1_1") (pintype "passive"))
      (node (ref "U400") (pin "58") (pinfunction "CLK_SEL_58") (pintype "passive"))
    )
    (net (code "38") (name "Net-(U400-DIN)") (class "Default")
      (node (ref "R419") (pin "2") (pinfunction "2_2") (pintype "passive"))
      (node (ref "U400") (pin "21") (pinfunction "DIN_21") (pintype "passive"))
    )
    (net (code "39") (name "Net-(U400-DOUT1)") (class "Default")
      (node (ref "R415") (pin "2") (pinfunction "2_2") (pintype "passive"))
      (node (ref "U400") (pin "26") (pinfunction "DOUT1_26") (pintype "passive"))
    )
    (net (code "40") (name "Net-(U400-DOUT2)") (class "Default")
      (node (ref "R416") (pin "2") (pinfunction "2_2") (pintype "passive"))
      (node (ref "U400") (pin "25") (pinfunction "DOUT2_25") (pintype "passive"))
    )
    (net (code "41") (name "Net-(U400-DOUT3)") (class "Default")
      (node (ref "R418") (pin "2") (pinfunction "2_2") (pintype "passive"))
      (node (ref "U400") (pin "24") (pinfunction "DOUT3_24") (pintype "passive"))
    )
    (net (code "42") (name "Net-(U400-DREGCAP)") (class "Default")
      (node (ref "C410") (pin "2") (pinfunction "2_2") (pintype "passive"))
      (node (ref "C411") (pin "1") (pinfunction "1_1") (pintype "passive"))
      (node (ref "U400") (pin "34") (pinfunction "DREGCAP_34") (pintype "passive"))
    )
    (net (code "43") (name "Net-(U400-FORMAT0)") (class "Default")
      (node (ref "R417") (pin "2") (pinfunction "2_2") (pintype "passive"))
      (node (ref "U400") (pin "56") (pinfunction "FORMAT0_56") (pintype "passive"))
    )
    (net (code "44") (name "Net-(U400-REGCAPA)") (class "Default")
      (node (ref "C408") (pin "2") (pinfunction "2_2") (pintype "passive"))
      (node (ref "C409") (pin "1") (pinfunction "1_1") (pintype "passive"))
      (node (ref "U400") (pin "61") (pinfunction "REGCAPA_61") (pintype "passive"))
    )
    (net (code "45") (name "Net-(U400-REGCAPB)") (class "Default")
      (node (ref "C405") (pin "2") (pinfunction "2_2") (pintype "passive"))
      (node (ref "C406") (pin "1") (pinfunction "1_1") (pintype "passive"))
      (node (ref "U400") (pin "52") (pinfunction "REGCAPB_52") (pintype "passive"))
    )
    (net (code "46") (name "Net-(U400-VCM)") (class "Default")
      (node (ref "R412") (pin "2") (pinfunction "2_2") (pintype "passive"))
      (node (ref "U400") (pin "59") (pinfunction "VCM_59") (pintype "passive"))
    )
    (net (code "47") (name "Net-(U400-XTAL1)") (class "Default")
      (node (ref "R427") (pin "2") (pinfunction "2_2") (pintype "passive"))
      (node (ref "U400") (pin "31") (pinfunction "XTAL1_31") (pintype "passive"))
    )
    (net (code "48") (name "Net-(U400-XTAL2{slash}MCLK)") (class "Default")
      (node (ref "C414") (pin "2") (pinfunction "2_2") (pintype "passive"))
      (node (ref "U400") (pin "32") (pinfunction "XTAL2/MCLK_32") (pintype "passive"))
      (node (ref "Y400") (pin "3") (pinfunction "Crystal_3") (pintype "passive"))
    )
    (net (code "49") (name "Net-(U400-~{SYNC_IN})") (class "Default")
      (node (ref "U400") (pin "36") (pinfunction "~{SYNC_IN}_36") (pintype "passive"))
      (node (ref "U400") (pin "38") (pinfunction "~{SYNC_OUT}_38") (pintype "passive"))
    )
    (net (code "50") (name "Net-(U401A-1IN-)") (class "Default")
      (node (ref "R400") (pin "1") (pinfunction "1_1") (pintype "passive"))
      (node (ref "R402") (pin "2") (pinfunction "2_2") (pintype "passive"))
      (node (ref "U401") (pin "2") (pinfunction "1IN-_2") (pintype "passive"))
    )
    (net (code "51") (name "Net-(U401A-1OUT)") (class "Default")
      (node (ref "R400") (pin "2") (pinfunction "2_2") (pintype "passive"))
      (node (ref "R401") (pin "1") (pinfunction "1_1") (pintype "passive"))
      (node (ref "U401") (pin "1") (pinfunction "1OUT_1") (pintype "passive"))
    )
    (net (code "52") (name "Net-(U401B-2IN-)") (class "Default")
      (node (ref "R404") (pin "2") (pinfunction "2_2") (pintype "passive"))
      (node (ref "R405") (pin "1") (pinfunction "1_1") (pintype "passive"))
      (node (ref "U401") (pin "6") (pinfunction "2IN-_6") (pintype "passive"))
    )
    (net (code "53") (name "Net-(U401B-2OUT)") (class "Default")
      (node (ref "R403") (pin "1") (pinfunction "1_1") (pintype "passive"))
      (node (ref "R405") (pin "2") (pinfunction "2_2") (pintype "passive"))
      (node (ref "U401") (pin "7") (pinfunction "2OUT_7") (pintype "passive"))
    )
    (net (code "54") (name "Net-(U402A-1IN-)") (class "Default")
      (node (ref "R406") (pin "1") (pinfunction "1_1") (pintype "passive"))
      (node (ref "R408") (pin "2") (pinfunction "2_2") (pintype "passive"))
      (node (ref "U402") (pin "2") (pinfunction "1IN-_2") (pintype "passive"))
    )
    (net (code "55") (name "Net-(U402A-1OUT)") (class "Default")
      (node (ref "R406") (pin "2") (pinfunction "2_2") (pintype "passive"))
      (node (ref "R407") (pin "1") (pinfunction "1_1") (pintype "passive"))
      (node (ref "U402") (pin "1") (pinfunction "1OUT_1") (pintype "passive"))
    )
    (net (code "56") (name "Net-(U402B-2IN-)") (class "Default")
      (node (ref "R410") (pin "2") (pinfunction "2_2") (pintype "passive"))
      (node (ref "R411") (pin "1") (pinfunction "1_1") (pintype "passive"))
      (node (ref "U402") (pin "6") (pinfunction "2IN-_6") (pintype "passive"))
    )
    (net (code "57") (name "Net-(U402B-2OUT)") (class "Default")
      (node (ref "R409") (pin "1") (pinfunction "1_1") (pintype "passive"))
      (node (ref "R411") (pin "2") (pinfunction "2_2") (pintype "passive"))
      (node (ref "U402") (pin "7") (pinfunction "2OUT_7") (pintype "passive"))
    )
    (net (code "58") (name "unconnected-(U400-DNC-Pad22)") (class "Default")
      (node (ref "U400") (pin "22") (pinfunction "DNC_22") (pintype "passive+no_connect"))
    )
    (net (code "59") (name "unconnected-(U400-DNC-Pad23)") (class "Default")
      (node (ref "U400") (pin "23") (pinfunction "DNC_23") (pintype "passive+no_connect"))
    )
  )
)
